# GWifi.net
KiCad netlist of a schematic drawn in EAGLE
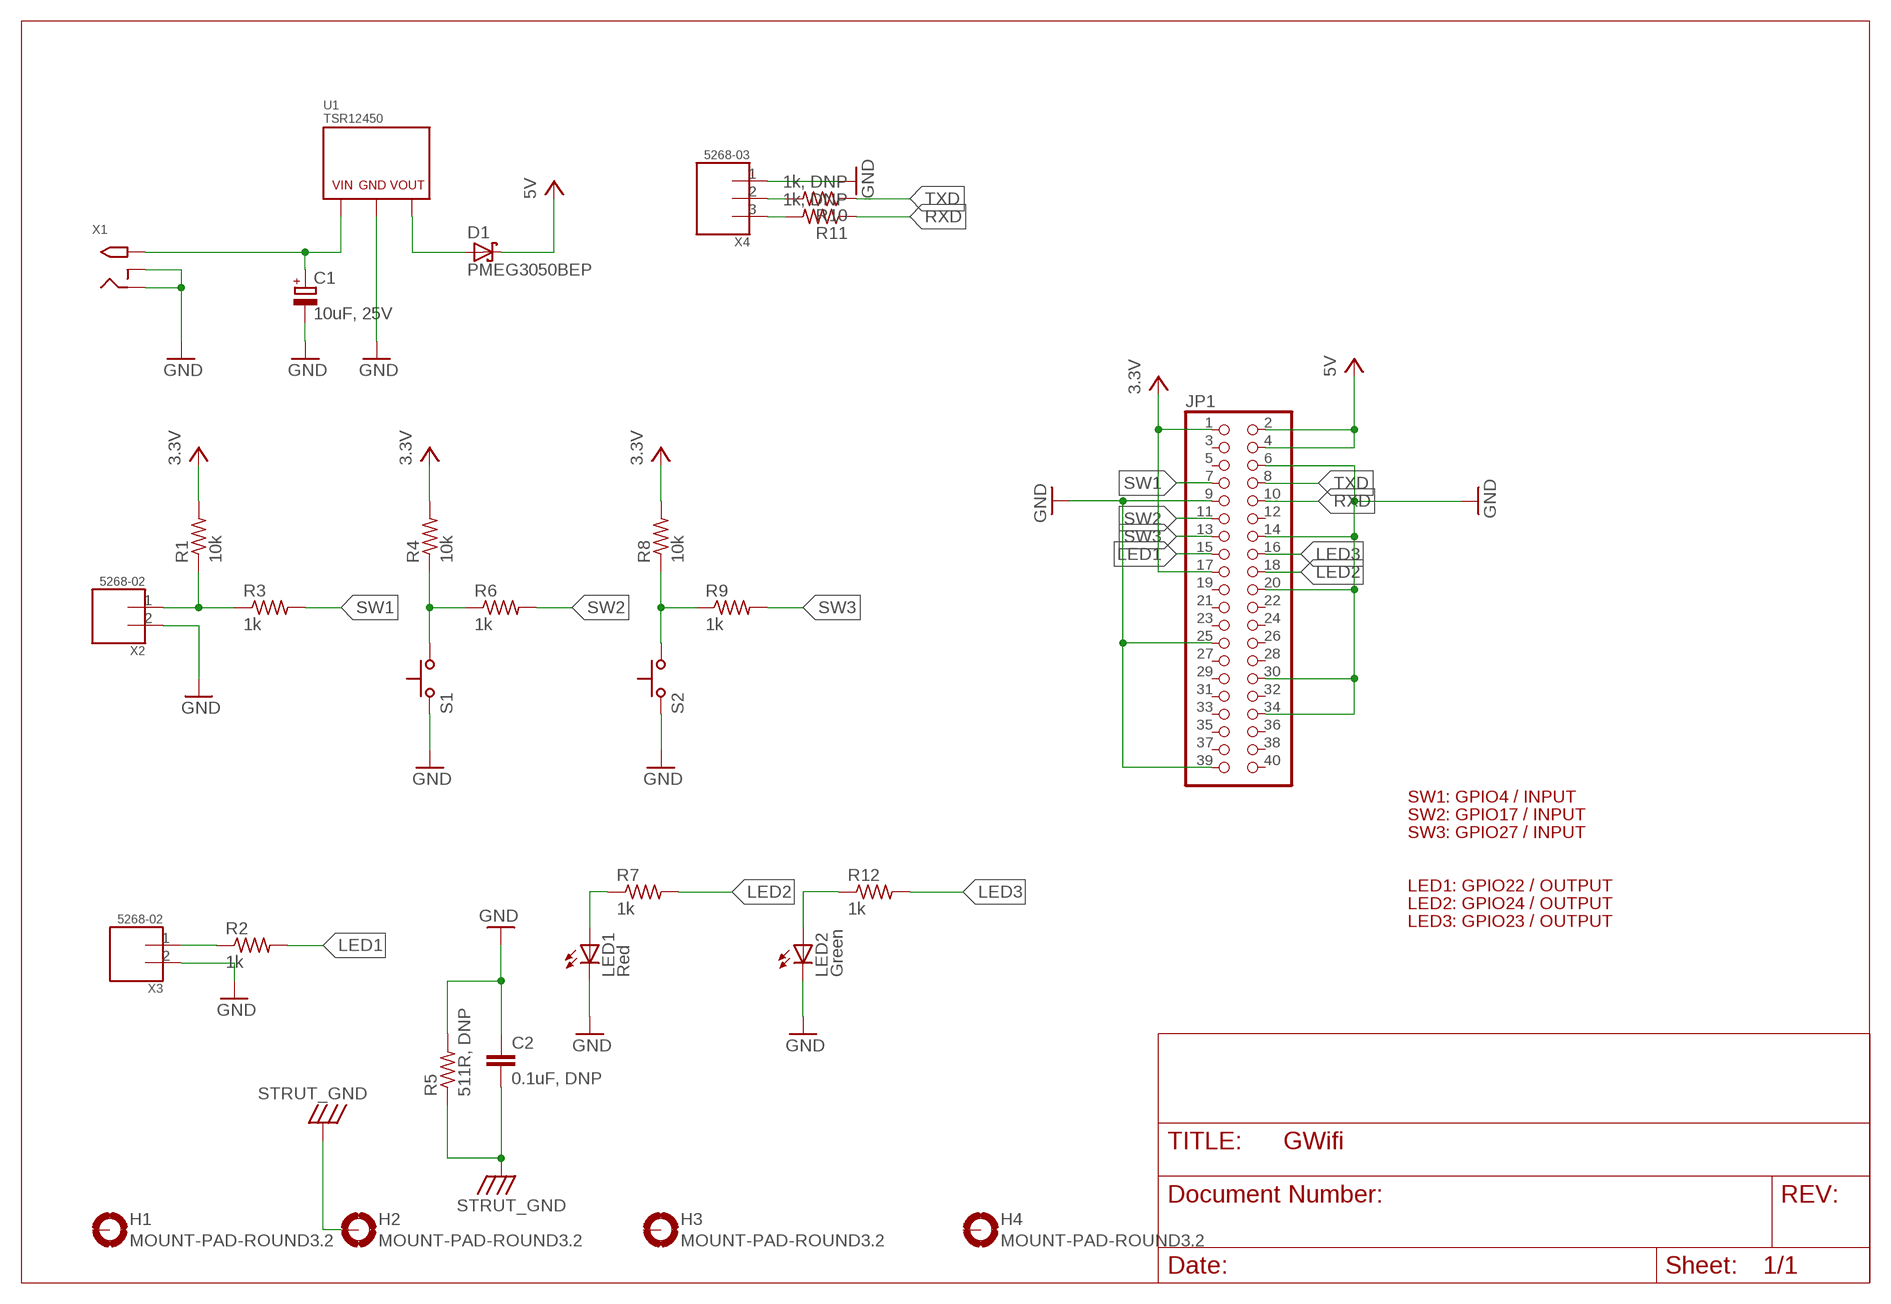
[diagram p0: schematic, sheet 1]

(export (version "E")
  (design (tool "Eeschema 10.0.6"))
  (components
    (comp (ref "C1")
      (value "10uF, 25V")
      (footprint "eagle-import:C3528-TR3B")
      (libsource (lib "eagle-import") (part "C-POL-TR3"))
    )
    (comp (ref "C2")
      (value "0.1uF, DNP")
      (footprint "eagle-import:C0805(2012)")
      (libsource (lib "eagle-import") (part "C0805(2012)"))
    )
    (comp (ref "D1")
      (value "PMEG3050BEP")
      (footprint "eagle-import:PMEG6020EP")
      (libsource (lib "eagle-import") (part "PMEG6020EP"))
    )
    (comp (ref "H1")
      (value "MOUNT-PAD-ROUND3.2")
      (footprint "eagle-import:3.2-PAD-ROUND")
      (libsource (lib "eagle-import") (part "MOUNT-PAD-ROUND3.2"))
    )
    (comp (ref "H2")
      (value "MOUNT-PAD-ROUND3.2")
      (footprint "eagle-import:3.2-PAD-ROUND")
      (libsource (lib "eagle-import") (part "MOUNT-PAD-ROUND3.2"))
    )
    (comp (ref "H3")
      (value "MOUNT-PAD-ROUND3.2")
      (footprint "eagle-import:3.2-PAD-ROUND")
      (libsource (lib "eagle-import") (part "MOUNT-PAD-ROUND3.2"))
    )
    (comp (ref "H4")
      (value "MOUNT-PAD-ROUND3.2")
      (footprint "eagle-import:3.2-PAD-ROUND")
      (libsource (lib "eagle-import") (part "MOUNT-PAD-ROUND3.2"))
    )
    (comp (ref "JP1")
      (value "PINHD-2X20")
      (footprint "eagle-import:2X20")
      (libsource (lib "eagle-import") (part "PINHD-2X20"))
    )
    (comp (ref "LED1")
      (value "Red")
      (footprint "eagle-import:LED3MM")
      (libsource (lib "eagle-import") (part "LED3MM"))
    )
    (comp (ref "LED2")
      (value "Green")
      (footprint "eagle-import:LED3MM")
      (libsource (lib "eagle-import") (part "LED3MM"))
    )
    (comp (ref "R1")
      (value "10k")
      (footprint "eagle-import:0805-THM")
      (libsource (lib "eagle-import") (part "R-US_FLIPFLOP"))
    )
    (comp (ref "R2")
      (value "1k")
      (footprint "eagle-import:0805-THM")
      (libsource (lib "eagle-import") (part "R-US_FLIPFLOP"))
    )
    (comp (ref "R3")
      (value "1k")
      (footprint "eagle-import:0805-THM")
      (libsource (lib "eagle-import") (part "R-US_FLIPFLOP"))
    )
    (comp (ref "R4")
      (value "10k")
      (footprint "eagle-import:0805-THM")
      (libsource (lib "eagle-import") (part "R-US_FLIPFLOP"))
    )
    (comp (ref "R5")
      (value "511R, DNP")
      (footprint "eagle-import:R0805(2012)")
      (libsource (lib "eagle-import") (part "R0805(2012)"))
    )
    (comp (ref "R6")
      (value "1k")
      (footprint "eagle-import:0805-THM")
      (libsource (lib "eagle-import") (part "R-US_FLIPFLOP"))
    )
    (comp (ref "R7")
      (value "1k")
      (footprint "eagle-import:0805-THM")
      (libsource (lib "eagle-import") (part "R-US_FLIPFLOP"))
    )
    (comp (ref "R8")
      (value "10k")
      (footprint "eagle-import:0805-THM")
      (libsource (lib "eagle-import") (part "R-US_FLIPFLOP"))
    )
    (comp (ref "R9")
      (value "1k")
      (footprint "eagle-import:0805-THM")
      (libsource (lib "eagle-import") (part "R-US_FLIPFLOP"))
    )
    (comp (ref "R10")
      (value "1k, DNP")
      (footprint "eagle-import:R0805(2012)")
      (libsource (lib "eagle-import") (part "R0805(2012)"))
    )
    (comp (ref "R11")
      (value "1k, DNP")
      (footprint "eagle-import:R0805(2012)")
      (libsource (lib "eagle-import") (part "R0805(2012)"))
    )
    (comp (ref "R12")
      (value "1k")
      (footprint "eagle-import:0805-THM")
      (libsource (lib "eagle-import") (part "R-US_FLIPFLOP"))
    )
    (comp (ref "S1")
      (value "SWITCH")
      (footprint "eagle-import:SKHLACA010")
      (libsource (lib "eagle-import") (part "SWITCH"))
    )
    (comp (ref "S2")
      (value "SWITCH")
      (footprint "eagle-import:SKHLACA010")
      (libsource (lib "eagle-import") (part "SWITCH"))
    )
    (comp (ref "U1")
      (value "TSR12450")
      (footprint "eagle-import:TSR12450")
      (libsource (lib "eagle-import") (part "TSR12450"))
    )
    (comp (ref "X1")
      (value "2.1MMJACKTHM")
      (footprint "eagle-import:PJ-102A")
      (libsource (lib "eagle-import") (part "2.1MMJACKTHM"))
    )
    (comp (ref "X2")
      (value "5268-02")
      (footprint "eagle-import:5628-02")
      (libsource (lib "eagle-import") (part "5268-02"))
    )
    (comp (ref "X3")
      (value "5268-02")
      (footprint "eagle-import:5628-02")
      (libsource (lib "eagle-import") (part "5268-02"))
    )
    (comp (ref "X4")
      (value "5268-03")
      (footprint "eagle-import:5268-03")
      (libsource (lib "eagle-import") (part "5268-03"))
    )
  )
  (nets
    (net (code "1") (name "3.3V") (class "Default")
      (node (ref "JP1") (pin "1") (pinfunction "1_1") (pintype "passive"))
      (node (ref "JP1") (pin "17") (pinfunction "17_17") (pintype "passive"))
      (node (ref "R1") (pin "2") (pinfunction "2_2") (pintype "passive"))
      (node (ref "R4") (pin "2") (pinfunction "2_2") (pintype "passive"))
      (node (ref "R8") (pin "2") (pinfunction "2_2") (pintype "passive"))
    )
    (net (code "2") (name "5V") (class "Default")
      (node (ref "D1") (pin "C") (pinfunction "C_C") (pintype "passive"))
      (node (ref "JP1") (pin "2") (pinfunction "2_2") (pintype "passive"))
      (node (ref "JP1") (pin "4") (pinfunction "4_4") (pintype "passive"))
    )
    (net (code "3") (name "GND") (class "Default")
      (node (ref "C1") (pin "-") (pinfunction "-_-") (pintype "passive"))
      (node (ref "C2") (pin "1") (pinfunction "1_1") (pintype "passive"))
      (node (ref "JP1") (pin "14") (pinfunction "14_14") (pintype "passive"))
      (node (ref "JP1") (pin "20") (pinfunction "20_20") (pintype "passive"))
      (node (ref "JP1") (pin "25") (pinfunction "25_25") (pintype "passive"))
      (node (ref "JP1") (pin "30") (pinfunction "30_30") (pintype "passive"))
      (node (ref "JP1") (pin "34") (pinfunction "34_34") (pintype "passive"))
      (node (ref "JP1") (pin "39") (pinfunction "39_39") (pintype "passive"))
      (node (ref "JP1") (pin "6") (pinfunction "6_6") (pintype "passive"))
      (node (ref "JP1") (pin "9") (pinfunction "9_9") (pintype "passive"))
      (node (ref "LED1") (pin "K") (pinfunction "C_K") (pintype "passive"))
      (node (ref "LED2") (pin "K") (pinfunction "C_K") (pintype "passive"))
      (node (ref "R5") (pin "2") (pinfunction "2_2") (pintype "passive"))
      (node (ref "S1") (pin "P$1") (pinfunction "P$1_P$1") (pintype "bidirectional"))
      (node (ref "S2") (pin "P$1") (pinfunction "P$1_P$1") (pintype "bidirectional"))
      (node (ref "U1") (pin "GND") (pinfunction "2_GND") (pintype "bidirectional"))
      (node (ref "X1") (pin "RING") (pinfunction "RING_RING") (pintype "bidirectional"))
      (node (ref "X1") (pin "RING_SW") (pinfunction "RING_SW_RING_SW") (pintype "bidirectional"))
      (node (ref "X2") (pin "2") (pinfunction "2_2") (pintype "bidirectional"))
      (node (ref "X3") (pin "2") (pinfunction "2_2") (pintype "bidirectional"))
      (node (ref "X4") (pin "1") (pinfunction "1_1") (pintype "bidirectional"))
    )
    (net (code "4") (name "LED1") (class "Default")
      (node (ref "JP1") (pin "15") (pinfunction "15_15") (pintype "passive"))
      (node (ref "R2") (pin "2") (pinfunction "2_2") (pintype "passive"))
    )
    (net (code "5") (name "LED2") (class "Default")
      (node (ref "JP1") (pin "18") (pinfunction "18_18") (pintype "passive"))
      (node (ref "R7") (pin "2") (pinfunction "2_2") (pintype "passive"))
    )
    (net (code "6") (name "LED3") (class "Default")
      (node (ref "JP1") (pin "16") (pinfunction "16_16") (pintype "passive"))
      (node (ref "R12") (pin "2") (pinfunction "2_2") (pintype "passive"))
    )
    (net (code "7") (name "Net-(LED1-PadA)") (class "Default")
      (node (ref "LED1") (pin "A") (pinfunction "A_A") (pintype "passive"))
      (node (ref "R7") (pin "1") (pinfunction "1_1") (pintype "passive"))
    )
    (net (code "8") (name "Net-(LED2-PadA)") (class "Default")
      (node (ref "LED2") (pin "A") (pinfunction "A_A") (pintype "passive"))
      (node (ref "R12") (pin "1") (pinfunction "1_1") (pintype "passive"))
    )
    (net (code "9") (name "Net-(R1-Pad1)") (class "Default")
      (node (ref "R1") (pin "1") (pinfunction "1_1") (pintype "passive"))
      (node (ref "R3") (pin "1") (pinfunction "1_1") (pintype "passive"))
      (node (ref "X2") (pin "1") (pinfunction "1_1") (pintype "bidirectional"))
    )
    (net (code "10") (name "Net-(R2-Pad1)") (class "Default")
      (node (ref "R2") (pin "1") (pinfunction "1_1") (pintype "passive"))
      (node (ref "X3") (pin "1") (pinfunction "1_1") (pintype "bidirectional"))
    )
    (net (code "11") (name "Net-(R4-Pad1)") (class "Default")
      (node (ref "R4") (pin "1") (pinfunction "1_1") (pintype "passive"))
      (node (ref "R6") (pin "1") (pinfunction "1_1") (pintype "passive"))
      (node (ref "S1") (pin "P$2") (pinfunction "P$2_P$2") (pintype "bidirectional"))
    )
    (net (code "12") (name "Net-(R8-Pad1)") (class "Default")
      (node (ref "R8") (pin "1") (pinfunction "1_1") (pintype "passive"))
      (node (ref "R9") (pin "1") (pinfunction "1_1") (pintype "passive"))
      (node (ref "S2") (pin "P$2") (pinfunction "P$2_P$2") (pintype "bidirectional"))
    )
    (net (code "13") (name "Net-(R10-Pad2)") (class "Default")
      (node (ref "R10") (pin "2") (pinfunction "2_2") (pintype "passive"))
      (node (ref "X4") (pin "2") (pinfunction "2_2") (pintype "bidirectional"))
    )
    (net (code "14") (name "Net-(R11-Pad2)") (class "Default")
      (node (ref "R11") (pin "2") (pinfunction "2_2") (pintype "passive"))
      (node (ref "X4") (pin "3") (pinfunction "3_3") (pintype "bidirectional"))
    )
    (net (code "15") (name "Net-(U1-1)") (class "Default")
      (node (ref "C1") (pin "+") (pinfunction "+_+") (pintype "passive"))
      (node (ref "U1") (pin "VIN") (pinfunction "1_VIN") (pintype "bidirectional"))
      (node (ref "X1") (pin "TIP") (pinfunction "TIP_TIP") (pintype "bidirectional"))
    )
    (net (code "16") (name "Net-(U1-3)") (class "Default")
      (node (ref "D1") (pin "A") (pinfunction "A_A") (pintype "passive"))
      (node (ref "U1") (pin "VOUT") (pinfunction "3_VOUT") (pintype "bidirectional"))
    )
    (net (code "17") (name "RXD") (class "Default")
      (node (ref "JP1") (pin "10") (pinfunction "10_10") (pintype "passive"))
      (node (ref "R11") (pin "1") (pinfunction "1_1") (pintype "passive"))
    )
    (net (code "18") (name "STRUT_GND") (class "Default")
      (node (ref "C2") (pin "2") (pinfunction "2_2") (pintype "passive"))
      (node (ref "H2") (pin "B3,2") (pinfunction "MOUNT_B3,2") (pintype "passive"))
      (node (ref "R5") (pin "1") (pinfunction "1_1") (pintype "passive"))
    )
    (net (code "19") (name "SW1") (class "Default")
      (node (ref "JP1") (pin "7") (pinfunction "7_7") (pintype "passive"))
      (node (ref "R3") (pin "2") (pinfunction "2_2") (pintype "passive"))
    )
    (net (code "20") (name "SW2") (class "Default")
      (node (ref "JP1") (pin "11") (pinfunction "11_11") (pintype "passive"))
      (node (ref "R6") (pin "2") (pinfunction "2_2") (pintype "passive"))
    )
    (net (code "21") (name "SW3") (class "Default")
      (node (ref "JP1") (pin "13") (pinfunction "13_13") (pintype "passive"))
      (node (ref "R9") (pin "2") (pinfunction "2_2") (pintype "passive"))
    )
    (net (code "22") (name "TXD") (class "Default")
      (node (ref "JP1") (pin "8") (pinfunction "8_8") (pintype "passive"))
      (node (ref "R10") (pin "1") (pinfunction "1_1") (pintype "passive"))
    )
    (net (code "23") (name "unconnected-(H1-MOUNT-PadB3,2)") (class "Default")
      (node (ref "H1") (pin "B3,2") (pinfunction "MOUNT_B3,2") (pintype "passive"))
    )
    (net (code "24") (name "unconnected-(H3-MOUNT-PadB3,2)") (class "Default")
      (node (ref "H3") (pin "B3,2") (pinfunction "MOUNT_B3,2") (pintype "passive"))
    )
    (net (code "25") (name "unconnected-(H4-MOUNT-PadB3,2)") (class "Default")
      (node (ref "H4") (pin "B3,2") (pinfunction "MOUNT_B3,2") (pintype "passive"))
    )
    (net (code "26") (name "unconnected-(JP1-Pad3)") (class "Default")
      (node (ref "JP1") (pin "3") (pinfunction "3_3") (pintype "passive"))
    )
    (net (code "27") (name "unconnected-(JP1-Pad5)") (class "Default")
      (node (ref "JP1") (pin "5") (pinfunction "5_5") (pintype "passive"))
    )
    (net (code "28") (name "unconnected-(JP1-Pad12)") (class "Default")
      (node (ref "JP1") (pin "12") (pinfunction "12_12") (pintype "passive"))
    )
    (net (code "29") (name "unconnected-(JP1-Pad19)") (class "Default")
      (node (ref "JP1") (pin "19") (pinfunction "19_19") (pintype "passive"))
    )
    (net (code "30") (name "unconnected-(JP1-Pad21)") (class "Default")
      (node (ref "JP1") (pin "21") (pinfunction "21_21") (pintype "passive"))
    )
    (net (code "31") (name "unconnected-(JP1-Pad22)") (class "Default")
      (node (ref "JP1") (pin "22") (pinfunction "22_22") (pintype "passive"))
    )
    (net (code "32") (name "unconnected-(JP1-Pad23)") (class "Default")
      (node (ref "JP1") (pin "23") (pinfunction "23_23") (pintype "passive"))
    )
    (net (code "33") (name "unconnected-(JP1-Pad24)") (class "Default")
      (node (ref "JP1") (pin "24") (pinfunction "24_24") (pintype "passive"))
    )
    (net (code "34") (name "unconnected-(JP1-Pad26)") (class "Default")
      (node (ref "JP1") (pin "26") (pinfunction "26_26") (pintype "passive"))
    )
    (net (code "35") (name "unconnected-(JP1-Pad27)") (class "Default")
      (node (ref "JP1") (pin "27") (pinfunction "27_27") (pintype "passive"))
    )
    (net (code "36") (name "unconnected-(JP1-Pad28)") (class "Default")
      (node (ref "JP1") (pin "28") (pinfunction "28_28") (pintype "passive"))
    )
    (net (code "37") (name "unconnected-(JP1-Pad29)") (class "Default")
      (node (ref "JP1") (pin "29") (pinfunction "29_29") (pintype "passive"))
    )
    (net (code "38") (name "unconnected-(JP1-Pad31)") (class "Default")
      (node (ref "JP1") (pin "31") (pinfunction "31_31") (pintype "passive"))
    )
    (net (code "39") (name "unconnected-(JP1-Pad32)") (class "Default")
      (node (ref "JP1") (pin "32") (pinfunction "32_32") (pintype "passive"))
    )
    (net (code "40") (name "unconnected-(JP1-Pad33)") (class "Default")
      (node (ref "JP1") (pin "33") (pinfunction "33_33") (pintype "passive"))
    )
    (net (code "41") (name "unconnected-(JP1-Pad35)") (class "Default")
      (node (ref "JP1") (pin "35") (pinfunction "35_35") (pintype "passive"))
    )
    (net (code "42") (name "unconnected-(JP1-Pad36)") (class "Default")
      (node (ref "JP1") (pin "36") (pinfunction "36_36") (pintype "passive"))
    )
    (net (code "43") (name "unconnected-(JP1-Pad37)") (class "Default")
      (node (ref "JP1") (pin "37") (pinfunction "37_37") (pintype "passive"))
    )
    (net (code "44") (name "unconnected-(JP1-Pad38)") (class "Default")
      (node (ref "JP1") (pin "38") (pinfunction "38_38") (pintype "passive"))
    )
    (net (code "45") (name "unconnected-(JP1-Pad40)") (class "Default")
      (node (ref "JP1") (pin "40") (pinfunction "40_40") (pintype "passive"))
    )
  )
)
